# RFM69_USB_Gateway_0_9.net
KiCad netlist of a schematic drawn in EAGLE
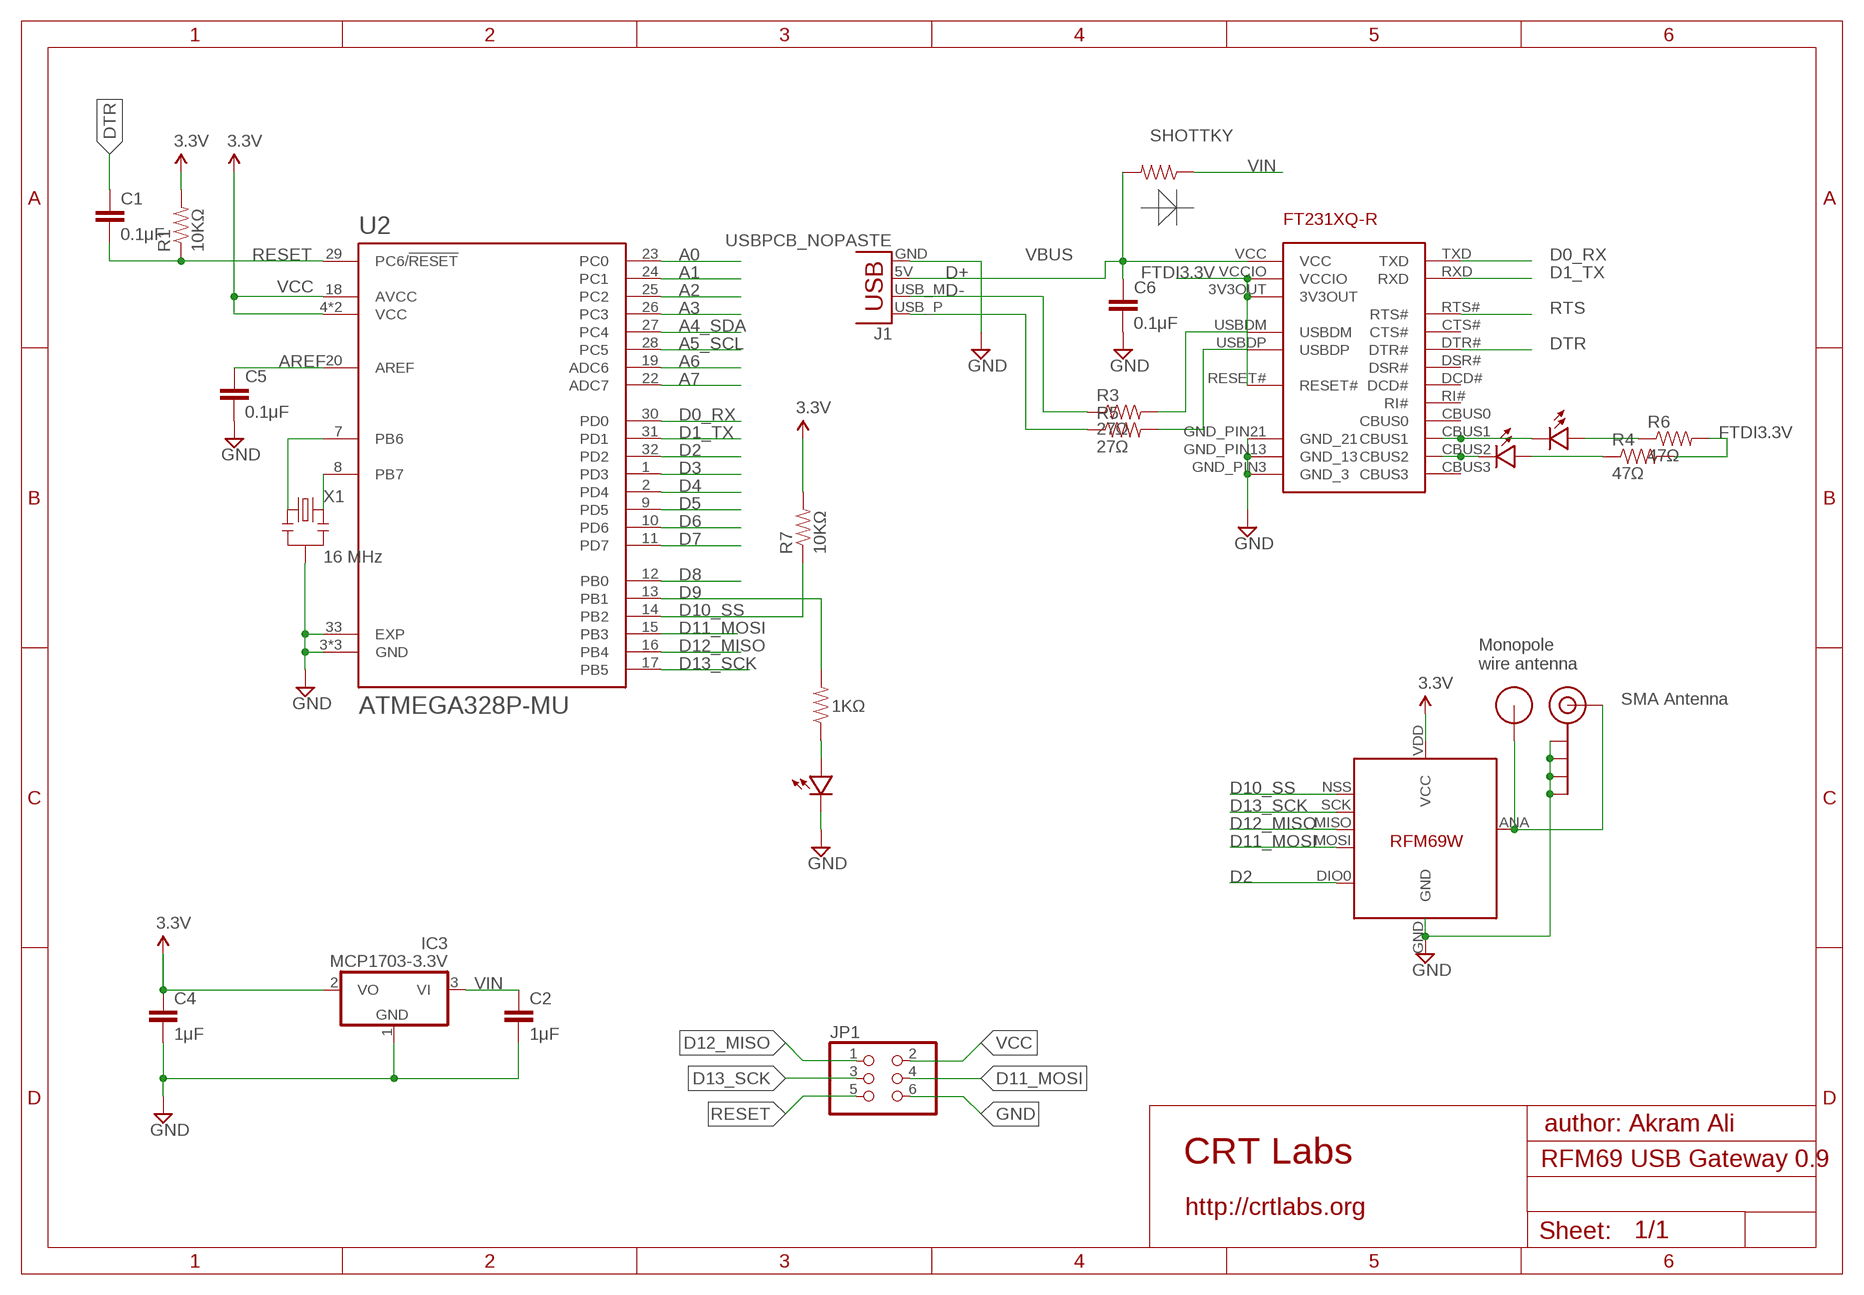
[diagram p0: schematic, sheet 1]

(export (version "E")
  (design (tool "Eeschema 10.0.6"))
  (components
    (comp (ref "C1")
      (value "0.1μF")
      (footprint "eagle-import:0805")
      (libsource (lib "eagle-import") (part "SparkFun_CAP0805"))
    )
    (comp (ref "C2")
      (value "1μF")
      (footprint "eagle-import:0805")
      (libsource (lib "eagle-import") (part "SparkFun_CAP0805"))
    )
    (comp (ref "C4")
      (value "1μF")
      (footprint "eagle-import:0805")
      (libsource (lib "eagle-import") (part "CAP0805"))
    )
    (comp (ref "C5")
      (value "0.1μF")
      (footprint "eagle-import:0805")
      (libsource (lib "eagle-import") (part "SparkFun_CAP0805"))
    )
    (comp (ref "C6")
      (value "0.1μF")
      (footprint "eagle-import:0805")
      (libsource (lib "eagle-import") (part "SparkFun_CAP0805"))
    )
    (comp (ref "D")
      (value "SHOTTKY")
      (footprint "eagle-import:0805")
      (libsource (lib "eagle-import") (part "RESISTOR0805"))
    )
    (comp (ref "FT231XQ-R")
      (value "FT231XQ-R")
      (footprint "eagle-import:FTDI_FT231XQ-R_PACKAGE")
      (libsource (lib "eagle-import") (part "FT231XQ-R"))
    )
    (comp (ref "IC3")
      (value "MCP1703-3.3V")
      (footprint "eagle-import:SOT23")
      (libsource (lib "eagle-import") (part "MCP1703CB"))
    )
    (comp (ref "J$1")
      (value "SMA_EDGE")
      (footprint "eagle-import:SMA-EDGE")
      (libsource (lib "eagle-import") (part "SMA_EDGE"))
    )
    (comp (ref "J1")
      (value "USBPCB_NOPASTE")
      (footprint "eagle-import:USB-A-PCB-NOPASTE")
      (libsource (lib "eagle-import") (part "USBPCB_NOPASTE"))
    )
    (comp (ref "JP1")
      (value "PINHD-2X3")
      (footprint "eagle-import:2X03")
      (libsource (lib "eagle-import") (part "PINHD-2X3"))
    )
    (comp (ref "R1")
      (value "10KΩ")
      (footprint "eagle-import:0805")
      (libsource (lib "eagle-import") (part "RESISTOR0805"))
    )
    (comp (ref "R2")
      (value "1KΩ")
      (footprint "eagle-import:0805")
      (libsource (lib "eagle-import") (part "SparkFun_RESISTOR0805-RES"))
    )
    (comp (ref "R3")
      (value "27Ω")
      (footprint "eagle-import:0805")
      (libsource (lib "eagle-import") (part "SparkFun_RESISTOR0805-RES"))
    )
    (comp (ref "R4")
      (value "47Ω")
      (footprint "eagle-import:0805")
      (libsource (lib "eagle-import") (part "SparkFun_RESISTOR0805-RES"))
    )
    (comp (ref "R5")
      (value "27Ω")
      (footprint "eagle-import:0805")
      (libsource (lib "eagle-import") (part "SparkFun_RESISTOR0805-RES"))
    )
    (comp (ref "R6")
      (value "47Ω")
      (footprint "eagle-import:0805")
      (libsource (lib "eagle-import") (part "SparkFun_RESISTOR0805-RES"))
    )
    (comp (ref "R7")
      (value "10KΩ")
      (footprint "eagle-import:0805")
      (libsource (lib "eagle-import") (part "SparkFun_RESISTOR0805-RES"))
    )
    (comp (ref "RX")
      (value "Green")
      (footprint "eagle-import:0805-LED")
      (libsource (lib "eagle-import") (part "LED0805"))
    )
    (comp (ref "TX")
      (value "Red")
      (footprint "eagle-import:0805-LED")
      (libsource (lib "eagle-import") (part "LED0805"))
    )
    (comp (ref "U$1")
      (value "RFM12B_ANTENNA")
      (footprint "eagle-import:RFM12B-ANTENNA")
      (libsource (lib "eagle-import") (part "RFM12B_ANTENNA"))
    )
    (comp (ref "U$2")
      (value "Status")
      (footprint "eagle-import:0805-LED")
      (libsource (lib "eagle-import") (part "LED0805"))
    )
    (comp (ref "U$5")
      (value "RFM69")
      (footprint "eagle-import:RFM69W-MINPADS")
      (libsource (lib "eagle-import") (part "RFM69"))
    )
    (comp (ref "U2")
      (value "ATMEGA328P-MU")
      (footprint "eagle-import:QFN50P500X500X100-33N")
      (fields (field (name "MF") "Atmel"))
      (libsource (lib "eagle-import") (part "ATMEGA328P-MU"))
    )
    (comp (ref "X1")
      (value "16 MHz")
      (footprint "eagle-import:RESONATOR-SMD")
      (libsource (lib "eagle-import") (part "RESONATORSMD"))
    )
  )
  (nets
    (net (code "1") (name "/A0") (class "Default")
      (node (ref "U2") (pin "23") (pinfunction "PC0_23") (pintype "bidirectional"))
    )
    (net (code "2") (name "/A1") (class "Default")
      (node (ref "U2") (pin "24") (pinfunction "PC1_24") (pintype "bidirectional"))
    )
    (net (code "3") (name "/A2") (class "Default")
      (node (ref "U2") (pin "25") (pinfunction "PC2_25") (pintype "bidirectional"))
    )
    (net (code "4") (name "/A3") (class "Default")
      (node (ref "U2") (pin "26") (pinfunction "PC3_26") (pintype "bidirectional"))
    )
    (net (code "5") (name "/A4_SDA") (class "Default")
      (node (ref "U2") (pin "27") (pinfunction "PC4_27") (pintype "bidirectional"))
    )
    (net (code "6") (name "/A5_SCL") (class "Default")
      (node (ref "U2") (pin "28") (pinfunction "PC5_28") (pintype "bidirectional"))
    )
    (net (code "7") (name "/A6") (class "Default")
      (node (ref "U2") (pin "19") (pinfunction "ADC6_19") (pintype "bidirectional"))
    )
    (net (code "8") (name "/A7") (class "Default")
      (node (ref "U2") (pin "22") (pinfunction "ADC7_22") (pintype "bidirectional"))
    )
    (net (code "9") (name "/AREF") (class "Default")
      (node (ref "C5") (pin "1") (pinfunction "1_1") (pintype "passive"))
      (node (ref "U2") (pin "20") (pinfunction "AREF_20") (pintype "input"))
    )
    (net (code "10") (name "/D+") (class "Default")
      (node (ref "J1") (pin "USB_P") (pinfunction "D+_USB_P") (pintype "bidirectional"))
      (node (ref "R5") (pin "1") (pinfunction "1_1") (pintype "passive"))
    )
    (net (code "11") (name "/D-") (class "Default")
      (node (ref "J1") (pin "USB_M") (pinfunction "D-_USB_M") (pintype "bidirectional"))
      (node (ref "R3") (pin "1") (pinfunction "1_1") (pintype "passive"))
    )
    (net (code "12") (name "/D0_RX") (class "Default")
      (node (ref "FT231XQ-R") (pin "TXD") (pinfunction "TXD_TXD") (pintype "bidirectional"))
      (node (ref "U2") (pin "30") (pinfunction "PD0_30") (pintype "bidirectional"))
    )
    (net (code "13") (name "/D1_TX") (class "Default")
      (node (ref "FT231XQ-R") (pin "RXD") (pinfunction "RXD_RXD") (pintype "bidirectional"))
      (node (ref "U2") (pin "31") (pinfunction "PD1_31") (pintype "bidirectional"))
    )
    (net (code "14") (name "/D2") (class "Default")
      (node (ref "U$5") (pin "DIO0") (pinfunction "DIO0_DIO0") (pintype "open_collector"))
      (node (ref "U2") (pin "32") (pinfunction "PD2_32") (pintype "bidirectional"))
    )
    (net (code "15") (name "/D3") (class "Default")
      (node (ref "U2") (pin "1") (pinfunction "PD3_1") (pintype "bidirectional"))
    )
    (net (code "16") (name "/D4") (class "Default")
      (node (ref "U2") (pin "2") (pinfunction "PD4_2") (pintype "bidirectional"))
    )
    (net (code "17") (name "/D5") (class "Default")
      (node (ref "U2") (pin "9") (pinfunction "PD5_9") (pintype "bidirectional"))
    )
    (net (code "18") (name "/D6") (class "Default")
      (node (ref "U2") (pin "10") (pinfunction "PD6_10") (pintype "bidirectional"))
    )
    (net (code "19") (name "/D7") (class "Default")
      (node (ref "U2") (pin "11") (pinfunction "PD7_11") (pintype "bidirectional"))
    )
    (net (code "20") (name "/D8") (class "Default")
      (node (ref "U2") (pin "12") (pinfunction "PB0_12") (pintype "bidirectional"))
    )
    (net (code "21") (name "/D9") (class "Default")
      (node (ref "R2") (pin "2") (pinfunction "2_2") (pintype "passive"))
      (node (ref "U2") (pin "13") (pinfunction "PB1_13") (pintype "bidirectional"))
    )
    (net (code "22") (name "/D10_SS") (class "Default")
      (node (ref "R7") (pin "1") (pinfunction "1_1") (pintype "passive"))
      (node (ref "U$5") (pin "NSS") (pinfunction "SEL_NSS") (pintype "input"))
      (node (ref "U2") (pin "14") (pinfunction "PB2_14") (pintype "bidirectional"))
    )
    (net (code "23") (name "/FTDI3.3V") (class "Default")
      (node (ref "FT231XQ-R") (pin "3V3OUT") (pinfunction "3V3OUT_3V3OUT") (pintype "bidirectional"))
      (node (ref "FT231XQ-R") (pin "RESET#") (pinfunction "RESET#_RESET#") (pintype "bidirectional"))
      (node (ref "FT231XQ-R") (pin "VCCIO") (pinfunction "VCCIO_VCCIO") (pintype "bidirectional"))
      (node (ref "R4") (pin "2") (pinfunction "2_2") (pintype "passive"))
      (node (ref "R6") (pin "2") (pinfunction "2_2") (pintype "passive"))
    )
    (net (code "24") (name "/RTS") (class "Default")
      (node (ref "FT231XQ-R") (pin "RTS#") (pinfunction "RTS#_RTS#") (pintype "bidirectional"))
    )
    (net (code "25") (name "/VBUS") (class "Default")
      (node (ref "C6") (pin "1") (pinfunction "1_1") (pintype "passive"))
      (node (ref "D") (pin "2") (pinfunction "2_2") (pintype "passive"))
      (node (ref "FT231XQ-R") (pin "VCC") (pinfunction "VCC_VCC") (pintype "bidirectional"))
      (node (ref "J1") (pin "5V") (pinfunction "VBUS_5V") (pintype "bidirectional"))
    )
    (net (code "26") (name "/VIN") (class "Default")
      (node (ref "C2") (pin "1") (pinfunction "1_1") (pintype "passive"))
      (node (ref "D") (pin "1") (pinfunction "1_1") (pintype "passive"))
      (node (ref "IC3") (pin "3") (pinfunction "VI_3") (pintype "input"))
    )
    (net (code "27") (name "D11_MOSI") (class "Default")
      (node (ref "JP1") (pin "4") (pinfunction "4_4") (pintype "passive"))
      (node (ref "U$5") (pin "MOSI") (pinfunction "MOSI_MOSI") (pintype "output"))
      (node (ref "U2") (pin "15") (pinfunction "PB3_15") (pintype "bidirectional"))
    )
    (net (code "28") (name "D12_MISO") (class "Default")
      (node (ref "JP1") (pin "1") (pinfunction "1_1") (pintype "passive"))
      (node (ref "U$5") (pin "MISO") (pinfunction "MISO_MISO") (pintype "input"))
      (node (ref "U2") (pin "16") (pinfunction "PB4_16") (pintype "bidirectional"))
    )
    (net (code "29") (name "D13_SCK") (class "Default")
      (node (ref "JP1") (pin "3") (pinfunction "3_3") (pintype "passive"))
      (node (ref "U$5") (pin "SCK") (pinfunction "SCK_SCK") (pintype "input"))
      (node (ref "U2") (pin "17") (pinfunction "PB5_17") (pintype "bidirectional"))
    )
    (net (code "30") (name "DTR") (class "Default")
      (node (ref "C1") (pin "1") (pinfunction "1_1") (pintype "passive"))
      (node (ref "FT231XQ-R") (pin "DTR#") (pinfunction "DTR#_DTR#") (pintype "bidirectional"))
    )
    (net (code "31") (name "GND") (class "Default")
      (node (ref "C2") (pin "2") (pinfunction "2_2") (pintype "passive"))
      (node (ref "C4") (pin "2") (pinfunction "2_2") (pintype "passive"))
      (node (ref "C5") (pin "2") (pinfunction "2_2") (pintype "passive"))
      (node (ref "C6") (pin "2") (pinfunction "2_2") (pintype "passive"))
      (node (ref "FT231XQ-R") (pin "GND_PIN13") (pinfunction "GND_13_GND_PIN13") (pintype "bidirectional"))
      (node (ref "FT231XQ-R") (pin "GND_PIN21") (pinfunction "GND_21_GND_PIN21") (pintype "bidirectional"))
      (node (ref "FT231XQ-R") (pin "GND_PIN3") (pinfunction "GND_3_GND_PIN3") (pintype "bidirectional"))
      (node (ref "IC3") (pin "1") (pinfunction "GND_1") (pintype "passive"))
      (node (ref "J$1") (pin "GND@0") (pinfunction "GND_GND@0") (pintype "bidirectional"))
      (node (ref "J$1") (pin "GND@1") (pinfunction "GND_GND@1") (pintype "bidirectional"))
      (node (ref "J$1") (pin "GND@2") (pinfunction "GND_GND@2") (pintype "bidirectional"))
      (node (ref "J$1") (pin "GND@3") (pinfunction "GND_GND@3") (pintype "bidirectional"))
      (node (ref "J1") (pin "GND") (pinfunction "GND_GND") (pintype "bidirectional"))
      (node (ref "JP1") (pin "6") (pinfunction "6_6") (pintype "passive"))
      (node (ref "U$2") (pin "MINUS") (pinfunction "MINUS_MINUS") (pintype "passive"))
      (node (ref "U$5") (pin "GND") (pinfunction "GND_GND") (pintype "power_in"))
      (node (ref "U2") (pin "21") (pinfunction "GND_21") (pintype "power_in"))
      (node (ref "U2") (pin "3") (pinfunction "GND_3") (pintype "power_in"))
      (node (ref "U2") (pin "33") (pinfunction "EXP_33") (pintype "power_in"))
      (node (ref "U2") (pin "5") (pinfunction "GND_5") (pintype "power_in"))
      (node (ref "X1") (pin "2") (pinfunction "2_2") (pintype "passive"))
    )
    (net (code "32") (name "Net-(FT231XQ-R-PadCBUS1)") (class "Default")
      (node (ref "FT231XQ-R") (pin "CBUS1") (pinfunction "CBUS1_CBUS1") (pintype "bidirectional"))
      (node (ref "RX") (pin "MINUS") (pinfunction "MINUS_MINUS") (pintype "passive"))
    )
    (net (code "33") (name "Net-(FT231XQ-R-PadCBUS2)") (class "Default")
      (node (ref "FT231XQ-R") (pin "CBUS2") (pinfunction "CBUS2_CBUS2") (pintype "bidirectional"))
      (node (ref "TX") (pin "MINUS") (pinfunction "MINUS_MINUS") (pintype "passive"))
    )
    (net (code "34") (name "Net-(FT231XQ-R-PadUSBDM)") (class "Default")
      (node (ref "FT231XQ-R") (pin "USBDM") (pinfunction "USBDM_USBDM") (pintype "bidirectional"))
      (node (ref "R3") (pin "2") (pinfunction "2_2") (pintype "passive"))
    )
    (net (code "35") (name "Net-(FT231XQ-R-PadUSBDP)") (class "Default")
      (node (ref "FT231XQ-R") (pin "USBDP") (pinfunction "USBDP_USBDP") (pintype "bidirectional"))
      (node (ref "R5") (pin "2") (pinfunction "2_2") (pintype "passive"))
    )
    (net (code "36") (name "Net-(J$1-SIGNAL)") (class "Default")
      (node (ref "J$1") (pin "SIG") (pinfunction "SIGNAL_SIG") (pintype "bidirectional"))
      (node (ref "U$1") (pin "P$1") (pinfunction "1_P$1") (pintype "bidirectional"))
      (node (ref "U$5") (pin "ANA") (pinfunction "ANT_ANA") (pintype "passive"))
    )
    (net (code "37") (name "Net-(R2-Pad1)") (class "Default")
      (node (ref "R2") (pin "1") (pinfunction "1_1") (pintype "passive"))
      (node (ref "U$2") (pin "PLUS") (pinfunction "PLUS_PLUS") (pintype "passive"))
    )
    (net (code "38") (name "Net-(R4-Pad1)") (class "Default")
      (node (ref "R4") (pin "1") (pinfunction "1_1") (pintype "passive"))
      (node (ref "TX") (pin "PLUS") (pinfunction "PLUS_PLUS") (pintype "passive"))
    )
    (net (code "39") (name "Net-(R6-Pad1)") (class "Default")
      (node (ref "R6") (pin "1") (pinfunction "1_1") (pintype "passive"))
      (node (ref "RX") (pin "PLUS") (pinfunction "PLUS_PLUS") (pintype "passive"))
    )
    (net (code "40") (name "Net-(U2-PB6)") (class "Default")
      (node (ref "U2") (pin "7") (pinfunction "PB6_7") (pintype "bidirectional"))
      (node (ref "X1") (pin "1") (pinfunction "1_1") (pintype "passive"))
    )
    (net (code "41") (name "Net-(U2-PB7)") (class "Default")
      (node (ref "U2") (pin "8") (pinfunction "PB7_8") (pintype "bidirectional"))
      (node (ref "X1") (pin "3") (pinfunction "3_3") (pintype "passive"))
    )
    (net (code "42") (name "RESET") (class "Default")
      (node (ref "C1") (pin "2") (pinfunction "2_2") (pintype "passive"))
      (node (ref "JP1") (pin "5") (pinfunction "5_5") (pintype "passive"))
      (node (ref "R1") (pin "1") (pinfunction "1_1") (pintype "passive"))
      (node (ref "U2") (pin "29") (pinfunction "PC6/~{RESET}_29") (pintype "bidirectional"))
    )
    (net (code "43") (name "VCC") (class "Default")
      (node (ref "C4") (pin "1") (pinfunction "1_1") (pintype "passive"))
      (node (ref "IC3") (pin "2") (pinfunction "VO_2") (pintype "passive"))
      (node (ref "JP1") (pin "2") (pinfunction "2_2") (pintype "passive"))
      (node (ref "R1") (pin "2") (pinfunction "2_2") (pintype "passive"))
      (node (ref "R7") (pin "2") (pinfunction "2_2") (pintype "passive"))
      (node (ref "U$5") (pin "VDD") (pinfunction "VCC_VDD") (pintype "power_in"))
      (node (ref "U2") (pin "18") (pinfunction "AVCC_18") (pintype "power_in"))
      (node (ref "U2") (pin "4") (pinfunction "VCC_4") (pintype "power_in"))
      (node (ref "U2") (pin "6") (pinfunction "VCC_6") (pintype "power_in"))
    )
    (net (code "44") (name "unconnected-(FT231XQ-R-PadCBUS0)") (class "Default")
      (node (ref "FT231XQ-R") (pin "CBUS0") (pinfunction "CBUS0_CBUS0") (pintype "bidirectional"))
    )
    (net (code "45") (name "unconnected-(FT231XQ-R-PadCBUS3)") (class "Default")
      (node (ref "FT231XQ-R") (pin "CBUS3") (pinfunction "CBUS3_CBUS3") (pintype "bidirectional"))
    )
    (net (code "46") (name "unconnected-(FT231XQ-R-PadCTS#)") (class "Default")
      (node (ref "FT231XQ-R") (pin "CTS#") (pinfunction "CTS#_CTS#") (pintype "bidirectional"))
    )
    (net (code "47") (name "unconnected-(FT231XQ-R-PadDCD#)") (class "Default")
      (node (ref "FT231XQ-R") (pin "DCD#") (pinfunction "DCD#_DCD#") (pintype "bidirectional"))
    )
    (net (code "48") (name "unconnected-(FT231XQ-R-PadDSR#)") (class "Default")
      (node (ref "FT231XQ-R") (pin "DSR#") (pinfunction "DSR#_DSR#") (pintype "bidirectional"))
    )
    (net (code "49") (name "unconnected-(FT231XQ-R-PadRI#)") (class "Default")
      (node (ref "FT231XQ-R") (pin "RI#") (pinfunction "RI#_RI#") (pintype "bidirectional"))
    )
  )
)
